# 1-9.net
KiCad netlist of a schematic drawn in EAGLE
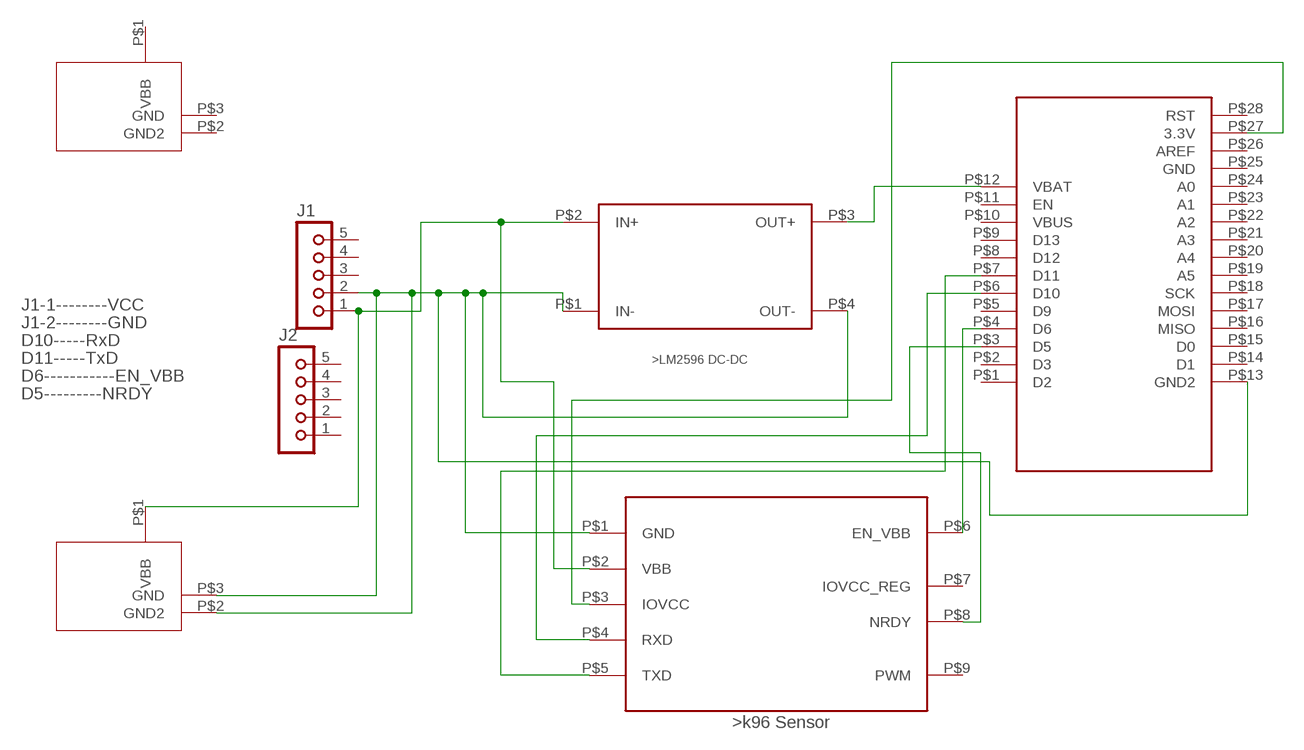
[diagram p0: schematic, sheet 1]

(export (version "E")
  (design (tool "Eeschema 10.0.6"))
  (components
    (comp (ref "DCDC1")
      (value "DCDC")
      (footprint "eagle-import:DCDC")
      (libsource (lib "eagle-import") (part "DCDC"))
    )
    (comp (ref "FEATHER1")
      (value "FEATHER")
      (footprint "eagle-import:FEATHER")
      (libsource (lib "eagle-import") (part "FEATHER"))
    )
    (comp (ref "J1")
      (value "JU05")
      (footprint "eagle-import:JU05")
      (libsource (lib "eagle-import") (part "JU05"))
    )
    (comp (ref "J2")
      (value "JU05")
      (footprint "eagle-import:JU05")
      (libsource (lib "eagle-import") (part "JU05"))
    )
    (comp (ref "K96SENSOR1")
      (value "K96SENSOR")
      (footprint "eagle-import:K96SENSOR")
      (libsource (lib "eagle-import") (part "K96SENSOR"))
    )
    (comp (ref "U$1")
      (value "POWER")
      (footprint "eagle-import:POWERIN")
      (libsource (lib "eagle-import") (part "POWER"))
    )
    (comp (ref "U$2")
      (value "POWER")
      (footprint "eagle-import:POWERIN")
      (libsource (lib "eagle-import") (part "POWER"))
    )
  )
  (nets
    (net (code "1") (name "Net-(DCDC1-IN+)") (class "Default")
      (node (ref "DCDC1") (pin "P$2") (pinfunction "IN+_P$2") (pintype "bidirectional"))
      (node (ref "J1") (pin "1") (pinfunction "1_1") (pintype "passive"))
      (node (ref "K96SENSOR1") (pin "P$2") (pinfunction "VBB_P$2") (pintype "bidirectional"))
      (node (ref "U$1") (pin "P$1") (pinfunction "VBB_P$1") (pintype "bidirectional"))
    )
    (net (code "2") (name "Net-(DCDC1-IN-)") (class "Default")
      (node (ref "DCDC1") (pin "P$1") (pinfunction "IN-_P$1") (pintype "bidirectional"))
      (node (ref "DCDC1") (pin "P$4") (pinfunction "OUT-_P$4") (pintype "bidirectional"))
      (node (ref "FEATHER1") (pin "P$13") (pinfunction "GND2_P$13") (pintype "bidirectional"))
      (node (ref "J1") (pin "2") (pinfunction "2_2") (pintype "passive"))
      (node (ref "K96SENSOR1") (pin "P$1") (pinfunction "GND_P$1") (pintype "bidirectional"))
      (node (ref "U$1") (pin "P$2") (pinfunction "GND2_P$2") (pintype "bidirectional"))
      (node (ref "U$1") (pin "P$3") (pinfunction "GND_P$3") (pintype "bidirectional"))
    )
    (net (code "3") (name "Net-(DCDC1-OUT+)") (class "Default")
      (node (ref "DCDC1") (pin "P$3") (pinfunction "OUT+_P$3") (pintype "bidirectional"))
      (node (ref "FEATHER1") (pin "P$12") (pinfunction "VBAT_P$12") (pintype "bidirectional"))
    )
    (net (code "4") (name "Net-(FEATHER1-3.3V)") (class "Default")
      (node (ref "FEATHER1") (pin "P$27") (pinfunction "3.3V_P$27") (pintype "bidirectional"))
      (node (ref "K96SENSOR1") (pin "P$3") (pinfunction "IOVCC_P$3") (pintype "bidirectional"))
    )
    (net (code "5") (name "Net-(FEATHER1-D5)") (class "Default")
      (node (ref "FEATHER1") (pin "P$3") (pinfunction "D5_P$3") (pintype "bidirectional"))
      (node (ref "K96SENSOR1") (pin "P$8") (pinfunction "NRDY_P$8") (pintype "bidirectional"))
    )
    (net (code "6") (name "Net-(FEATHER1-D6)") (class "Default")
      (node (ref "FEATHER1") (pin "P$4") (pinfunction "D6_P$4") (pintype "bidirectional"))
      (node (ref "K96SENSOR1") (pin "P$6") (pinfunction "EN_VBB_P$6") (pintype "bidirectional"))
    )
    (net (code "7") (name "Net-(FEATHER1-D10)") (class "Default")
      (node (ref "FEATHER1") (pin "P$6") (pinfunction "D10_P$6") (pintype "bidirectional"))
      (node (ref "K96SENSOR1") (pin "P$4") (pinfunction "RXD_P$4") (pintype "bidirectional"))
    )
    (net (code "8") (name "Net-(FEATHER1-D11)") (class "Default")
      (node (ref "FEATHER1") (pin "P$7") (pinfunction "D11_P$7") (pintype "bidirectional"))
      (node (ref "K96SENSOR1") (pin "P$5") (pinfunction "TXD_P$5") (pintype "bidirectional"))
    )
    (net (code "9") (name "unconnected-(FEATHER1-A0-PadP$24)") (class "Default")
      (node (ref "FEATHER1") (pin "P$24") (pinfunction "A0_P$24") (pintype "bidirectional"))
    )
    (net (code "10") (name "unconnected-(FEATHER1-A1-PadP$23)") (class "Default")
      (node (ref "FEATHER1") (pin "P$23") (pinfunction "A1_P$23") (pintype "bidirectional"))
    )
    (net (code "11") (name "unconnected-(FEATHER1-A2-PadP$22)") (class "Default")
      (node (ref "FEATHER1") (pin "P$22") (pinfunction "A2_P$22") (pintype "bidirectional"))
    )
    (net (code "12") (name "unconnected-(FEATHER1-A3-PadP$21)") (class "Default")
      (node (ref "FEATHER1") (pin "P$21") (pinfunction "A3_P$21") (pintype "bidirectional"))
    )
    (net (code "13") (name "unconnected-(FEATHER1-A4-PadP$20)") (class "Default")
      (node (ref "FEATHER1") (pin "P$20") (pinfunction "A4_P$20") (pintype "bidirectional"))
    )
    (net (code "14") (name "unconnected-(FEATHER1-A5-PadP$19)") (class "Default")
      (node (ref "FEATHER1") (pin "P$19") (pinfunction "A5_P$19") (pintype "bidirectional"))
    )
    (net (code "15") (name "unconnected-(FEATHER1-AREF-PadP$26)") (class "Default")
      (node (ref "FEATHER1") (pin "P$26") (pinfunction "AREF_P$26") (pintype "bidirectional"))
    )
    (net (code "16") (name "unconnected-(FEATHER1-D0-PadP$15)") (class "Default")
      (node (ref "FEATHER1") (pin "P$15") (pinfunction "D0_P$15") (pintype "bidirectional"))
    )
    (net (code "17") (name "unconnected-(FEATHER1-D1-PadP$14)") (class "Default")
      (node (ref "FEATHER1") (pin "P$14") (pinfunction "D1_P$14") (pintype "bidirectional"))
    )
    (net (code "18") (name "unconnected-(FEATHER1-D2-PadP$1)") (class "Default")
      (node (ref "FEATHER1") (pin "P$1") (pinfunction "D2_P$1") (pintype "bidirectional"))
    )
    (net (code "19") (name "unconnected-(FEATHER1-D3-PadP$2)") (class "Default")
      (node (ref "FEATHER1") (pin "P$2") (pinfunction "D3_P$2") (pintype "bidirectional"))
    )
    (net (code "20") (name "unconnected-(FEATHER1-D9-PadP$5)") (class "Default")
      (node (ref "FEATHER1") (pin "P$5") (pinfunction "D9_P$5") (pintype "bidirectional"))
    )
    (net (code "21") (name "unconnected-(FEATHER1-D12-PadP$8)") (class "Default")
      (node (ref "FEATHER1") (pin "P$8") (pinfunction "D12_P$8") (pintype "bidirectional"))
    )
    (net (code "22") (name "unconnected-(FEATHER1-D13-PadP$9)") (class "Default")
      (node (ref "FEATHER1") (pin "P$9") (pinfunction "D13_P$9") (pintype "bidirectional"))
    )
    (net (code "23") (name "unconnected-(FEATHER1-EN-PadP$11)") (class "Default")
      (node (ref "FEATHER1") (pin "P$11") (pinfunction "EN_P$11") (pintype "bidirectional"))
    )
    (net (code "24") (name "unconnected-(FEATHER1-GND-PadP$25)") (class "Default")
      (node (ref "FEATHER1") (pin "P$25") (pinfunction "GND_P$25") (pintype "bidirectional"))
    )
    (net (code "25") (name "unconnected-(FEATHER1-MISO-PadP$16)") (class "Default")
      (node (ref "FEATHER1") (pin "P$16") (pinfunction "MISO_P$16") (pintype "bidirectional"))
    )
    (net (code "26") (name "unconnected-(FEATHER1-MOSI-PadP$17)") (class "Default")
      (node (ref "FEATHER1") (pin "P$17") (pinfunction "MOSI_P$17") (pintype "bidirectional"))
    )
    (net (code "27") (name "unconnected-(FEATHER1-RST-PadP$28)") (class "Default")
      (node (ref "FEATHER1") (pin "P$28") (pinfunction "RST_P$28") (pintype "bidirectional"))
    )
    (net (code "28") (name "unconnected-(FEATHER1-SCK-PadP$18)") (class "Default")
      (node (ref "FEATHER1") (pin "P$18") (pinfunction "SCK_P$18") (pintype "bidirectional"))
    )
    (net (code "29") (name "unconnected-(FEATHER1-VBUS-PadP$10)") (class "Default")
      (node (ref "FEATHER1") (pin "P$10") (pinfunction "VBUS_P$10") (pintype "bidirectional"))
    )
    (net (code "30") (name "unconnected-(J1-Pad3)") (class "Default")
      (node (ref "J1") (pin "3") (pinfunction "3_3") (pintype "passive"))
    )
    (net (code "31") (name "unconnected-(J1-Pad4)") (class "Default")
      (node (ref "J1") (pin "4") (pinfunction "4_4") (pintype "passive"))
    )
    (net (code "32") (name "unconnected-(J1-Pad5)") (class "Default")
      (node (ref "J1") (pin "5") (pinfunction "5_5") (pintype "passive"))
    )
    (net (code "33") (name "unconnected-(J2-Pad1)") (class "Default")
      (node (ref "J2") (pin "1") (pinfunction "1_1") (pintype "passive"))
    )
    (net (code "34") (name "unconnected-(J2-Pad2)") (class "Default")
      (node (ref "J2") (pin "2") (pinfunction "2_2") (pintype "passive"))
    )
    (net (code "35") (name "unconnected-(J2-Pad3)") (class "Default")
      (node (ref "J2") (pin "3") (pinfunction "3_3") (pintype "passive"))
    )
    (net (code "36") (name "unconnected-(J2-Pad4)") (class "Default")
      (node (ref "J2") (pin "4") (pinfunction "4_4") (pintype "passive"))
    )
    (net (code "37") (name "unconnected-(J2-Pad5)") (class "Default")
      (node (ref "J2") (pin "5") (pinfunction "5_5") (pintype "passive"))
    )
    (net (code "38") (name "unconnected-(K96SENSOR1-IOVCC_REG-PadP$7)") (class "Default")
      (node (ref "K96SENSOR1") (pin "P$7") (pinfunction "IOVCC_REG_P$7") (pintype "bidirectional"))
    )
    (net (code "39") (name "unconnected-(K96SENSOR1-PWM-PadP$9)") (class "Default")
      (node (ref "K96SENSOR1") (pin "P$9") (pinfunction "PWM_P$9") (pintype "bidirectional"))
    )
    (net (code "40") (name "unconnected-(U$2-GND-PadP$3)") (class "Default")
      (node (ref "U$2") (pin "P$3") (pinfunction "GND_P$3") (pintype "bidirectional"))
    )
    (net (code "41") (name "unconnected-(U$2-GND2-PadP$2)") (class "Default")
      (node (ref "U$2") (pin "P$2") (pinfunction "GND2_P$2") (pintype "bidirectional"))
    )
    (net (code "42") (name "unconnected-(U$2-VBB-PadP$1)") (class "Default")
      (node (ref "U$2") (pin "P$1") (pinfunction "VBB_P$1") (pintype "bidirectional"))
    )
  )
)
